# OpenRing_MPU.net
KiCad netlist of a schematic drawn in Altium Designer
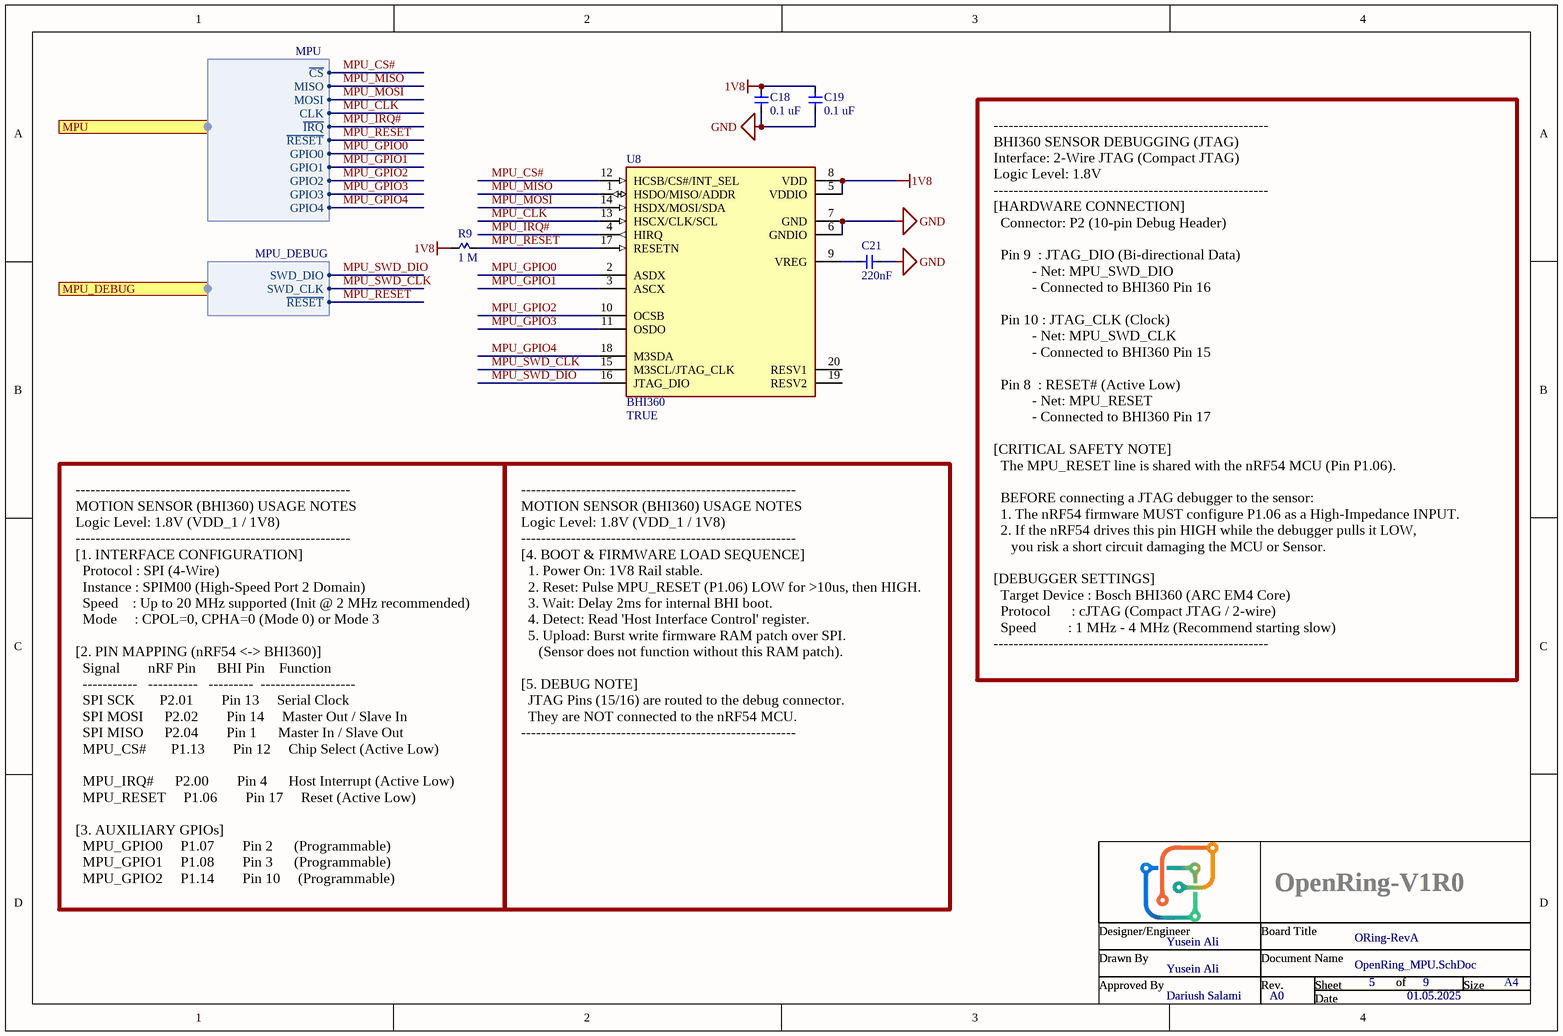
[diagram p0: OpenRing_MPU.SchDoc]

(export (version "E")
  (design (tool "Eeschema 10.0.6"))
  (components
    (comp (ref "C18")
      (value "0.1 uF")
      (footprint "CAPC1005X05N")
      (description "CAP CER 0.1UF 16V X5R 0402")
      (fields
        (field (name "MANUFACTURER") "Murata Electronics")
        (field (name "MANUFACTURER PART NUMBER") "GRM155R61C104KA88D")
      )
      (libsource (lib "OpenRingComponents") (part "GRM155R61C104KA88D"))
    )
    (comp (ref "C19")
      (value "0.1 uF")
      (footprint "CAPC1005X05N")
      (description "CAP CER 0.1UF 16V X5R 0402")
      (fields
        (field (name "MANUFACTURER") "Murata Electronics")
        (field (name "MANUFACTURER PART NUMBER") "GRM155R61C104KA88D")
      )
      (libsource (lib "OpenRingComponents") (part "GRM155R61C104KA88D"))
    )
    (comp (ref "C21")
      (value "220nF")
      (footprint "CAPC1005X05N")
      (description "CAP CER 0.22UF 16V X5R 0402")
      (fields
        (field (name "MANUFACTURER") "Murata")
        (field (name "MANUFACTURER PART NUMBER") "GRM155R61C224KA12D")
      )
      (libsource (lib "OpenRingComponents") (part "GRM155R61C224KA12D"))
    )
    (comp (ref "R9")
      (value "1 M")
      (footprint "RESC1005X04N")
      (description "RES SMD 1M OHM 1% 1/10W 0402")
      (fields
        (field (name "MANUFACTURER") "Panasonic Electronic Components")
        (field (name "MANUFACTURER PART NUMBER") "ERJ-2RKF1004X")
      )
      (libsource (lib "OpenRingComponents") (part "ERJ-2RKF1004X"))
    )
    (comp (ref "U8")
      (value "BHI360")
      (footprint "BHI360")
      (description "Programmable smart sensor combining accelerometer, gyroscope and fusion software")
      (fields (field (name "MANUFACTURER") "Bosch Tools") (field (name "CHECKED") "TRUE"))
      (libsource (lib "ICs") (part "BHI360"))
    )
  )
  (nets
    (net (code "3") (name "/MPU_CLK") (class "Default")
      (node (ref "U8") (pin "13") (pinfunction "HSCX/CLK/SCL_13") (pintype "input"))
    )
    (net (code "4") (name "/MPU_CS#") (class "Default")
      (node (ref "U8") (pin "12") (pinfunction "HCSB/CS#/INT_SEL_12") (pintype "input"))
    )
    (net (code "5") (name "/MPU_GPIO0") (class "Default")
      (node (ref "U8") (pin "2") (pinfunction "ASDX_2") (pintype "passive"))
    )
    (net (code "6") (name "/MPU_GPIO1") (class "Default")
      (node (ref "U8") (pin "3") (pinfunction "ASCX_3") (pintype "passive"))
    )
    (net (code "7") (name "/MPU_GPIO2") (class "Default")
      (node (ref "U8") (pin "10") (pinfunction "OCSB_10") (pintype "passive"))
    )
    (net (code "8") (name "/MPU_GPIO3") (class "Default")
      (node (ref "U8") (pin "11") (pinfunction "OSDO_11") (pintype "passive"))
    )
    (net (code "9") (name "/MPU_GPIO4") (class "Default")
      (node (ref "U8") (pin "18") (pinfunction "M3SDA_18") (pintype "passive"))
    )
    (net (code "10") (name "/MPU_IRQ#") (class "Default")
      (node (ref "U8") (pin "4") (pinfunction "HIRQ_4") (pintype "output"))
    )
    (net (code "11") (name "/MPU_MISO") (class "Default")
      (node (ref "U8") (pin "1") (pinfunction "HSDO/MISO/ADDR_1") (pintype "bidirectional"))
    )
    (net (code "12") (name "/MPU_MOSI") (class "Default")
      (node (ref "U8") (pin "14") (pinfunction "HSDX/MOSI/SDA_14") (pintype "input"))
    )
    (net (code "13") (name "/MPU_SWD_CLK") (class "Default")
      (node (ref "U8") (pin "15") (pinfunction "M3SCL/JTAG_CLK_15") (pintype "passive"))
    )
    (net (code "14") (name "/MPU_SWD_DIO") (class "Default")
      (node (ref "U8") (pin "16") (pinfunction "JTAG_DIO_16") (pintype "passive"))
    )
    (net (code "15") (name "/MPU_~{RESET}") (class "Default")
      (node (ref "R9") (pin "2") (pinfunction "2_2") (pintype "passive"))
      (node (ref "U8") (pin "17") (pinfunction "RESETN_17") (pintype "input"))
    )
    (net (code "18") (name "1V8") (class "Default")
      (node (ref "C18") (pin "2") (pinfunction "2_2") (pintype "passive"))
      (node (ref "C19") (pin "2") (pinfunction "2_2") (pintype "passive"))
      (node (ref "R9") (pin "1") (pinfunction "1_1") (pintype "passive"))
      (node (ref "U8") (pin "5") (pinfunction "VDDIO_5") (pintype "passive"))
      (node (ref "U8") (pin "8") (pinfunction "VDD_8") (pintype "passive"))
    )
    (net (code "19") (name "GND") (class "Default")
      (node (ref "C18") (pin "1") (pinfunction "1_1") (pintype "passive"))
      (node (ref "C19") (pin "1") (pinfunction "1_1") (pintype "passive"))
      (node (ref "C21") (pin "2") (pinfunction "2_2") (pintype "passive"))
      (node (ref "U8") (pin "6") (pinfunction "GNDIO_6") (pintype "passive"))
      (node (ref "U8") (pin "7") (pinfunction "GND_7") (pintype "passive"))
    )
    (net (code "20") (name "Net-(U8-VREG)") (class "Default")
      (node (ref "C21") (pin "1") (pinfunction "1_1") (pintype "passive"))
      (node (ref "U8") (pin "9") (pinfunction "VREG_9") (pintype "passive"))
    )
    (net (code "21") (name "unconnected-(U8-RESV1-Pad20)") (class "Default")
      (node (ref "U8") (pin "20") (pinfunction "RESV1_20") (pintype "passive"))
    )
    (net (code "22") (name "unconnected-(U8-RESV2-Pad19)") (class "Default")
      (node (ref "U8") (pin "19") (pinfunction "RESV2_19") (pintype "passive"))
    )
  )
)
